# design.net
KiCad netlist of a schematic drawn in Altium Designer
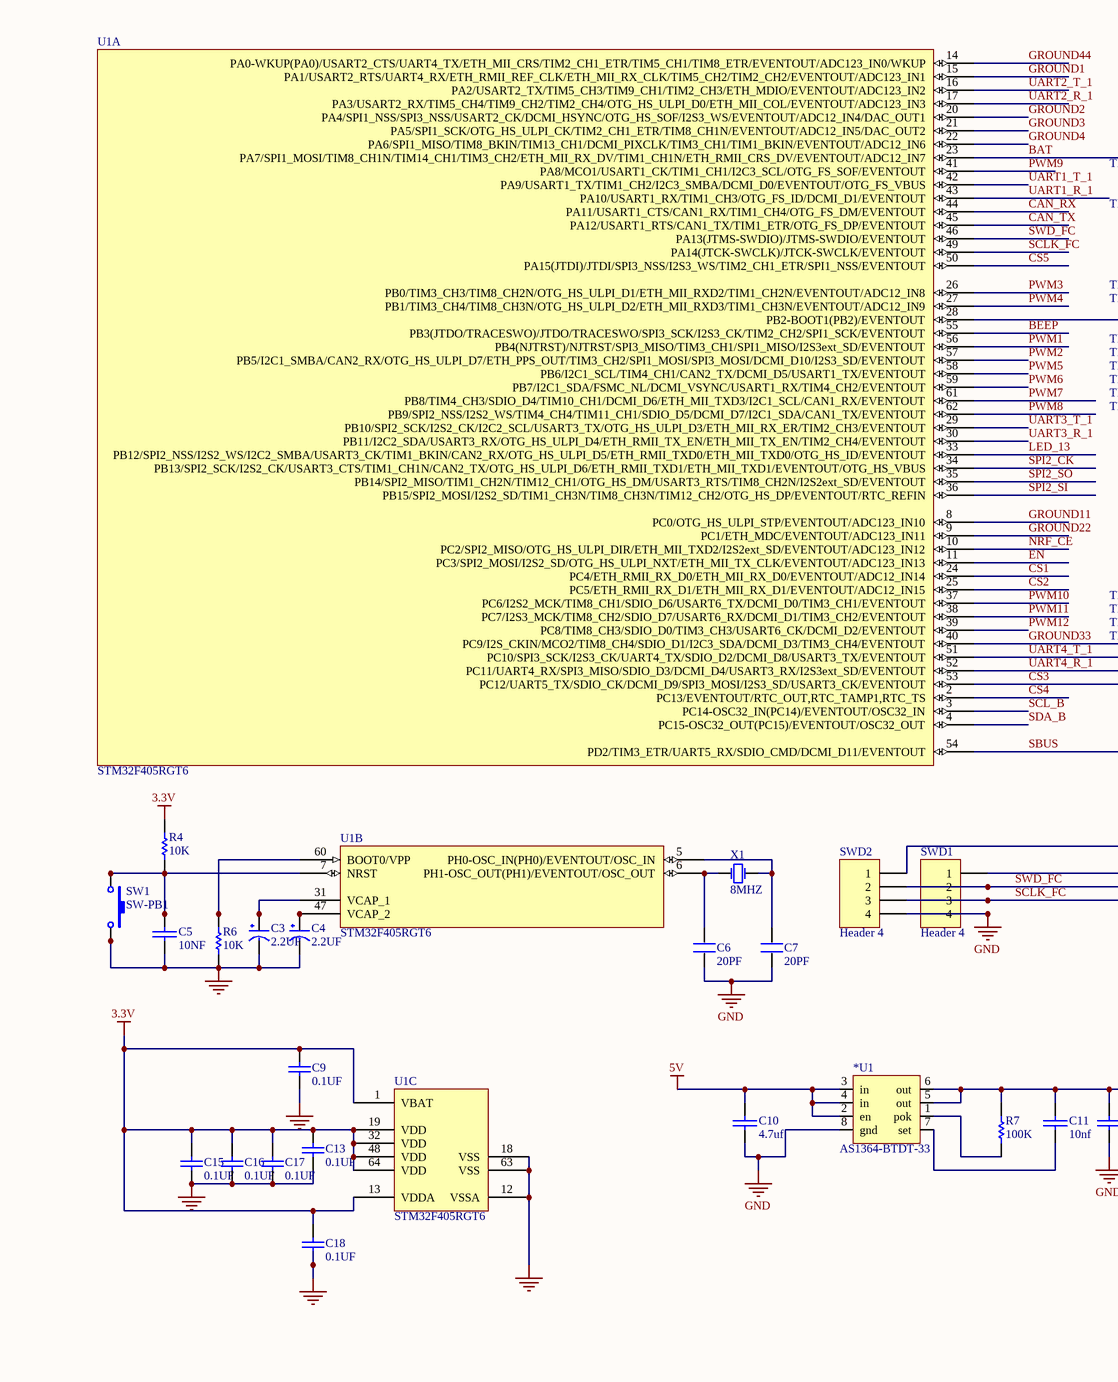
[diagram p0: 主控制器.SchDoc, top left]
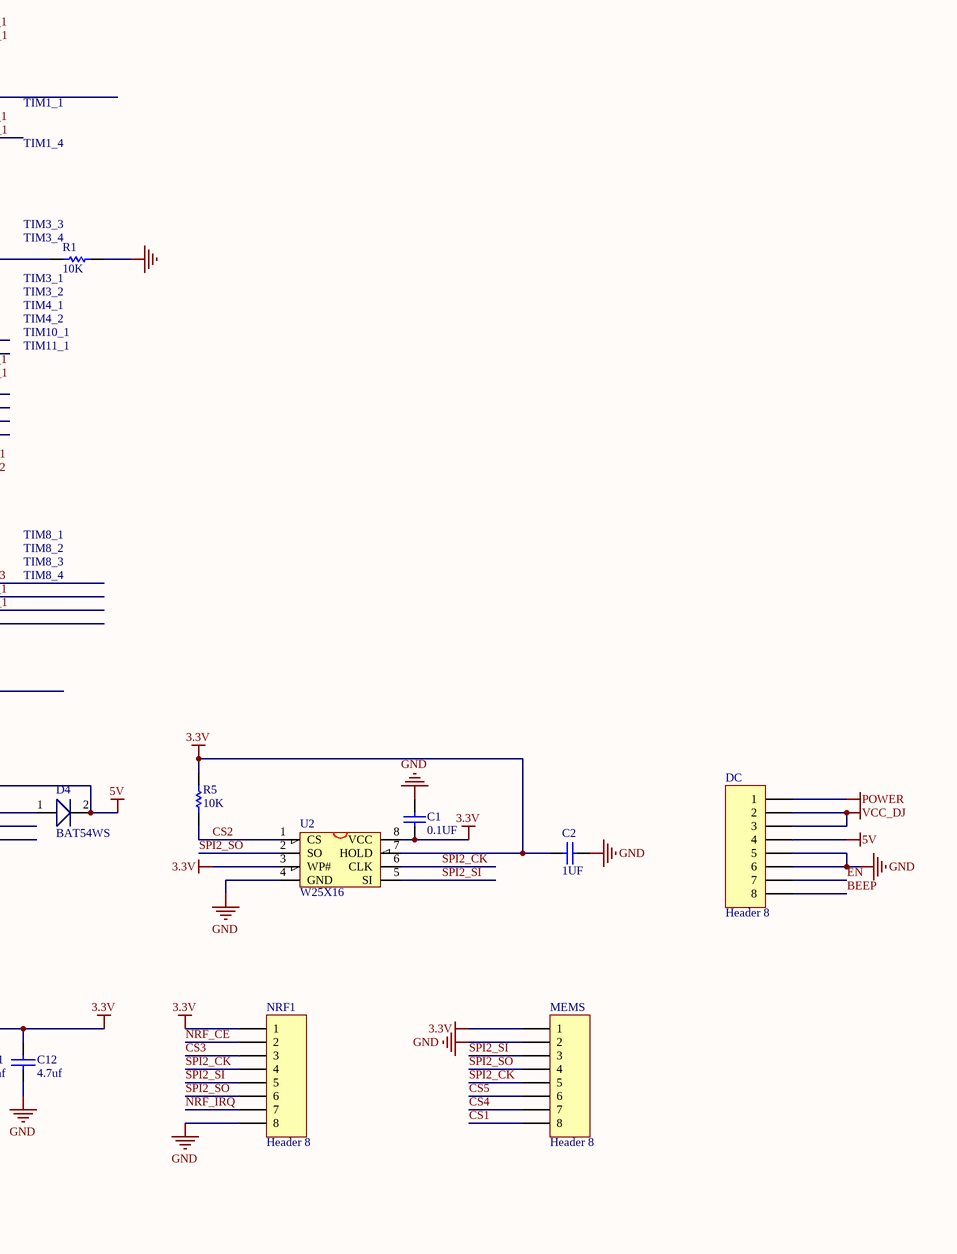
[diagram p1: 主控制器.SchDoc, top right]
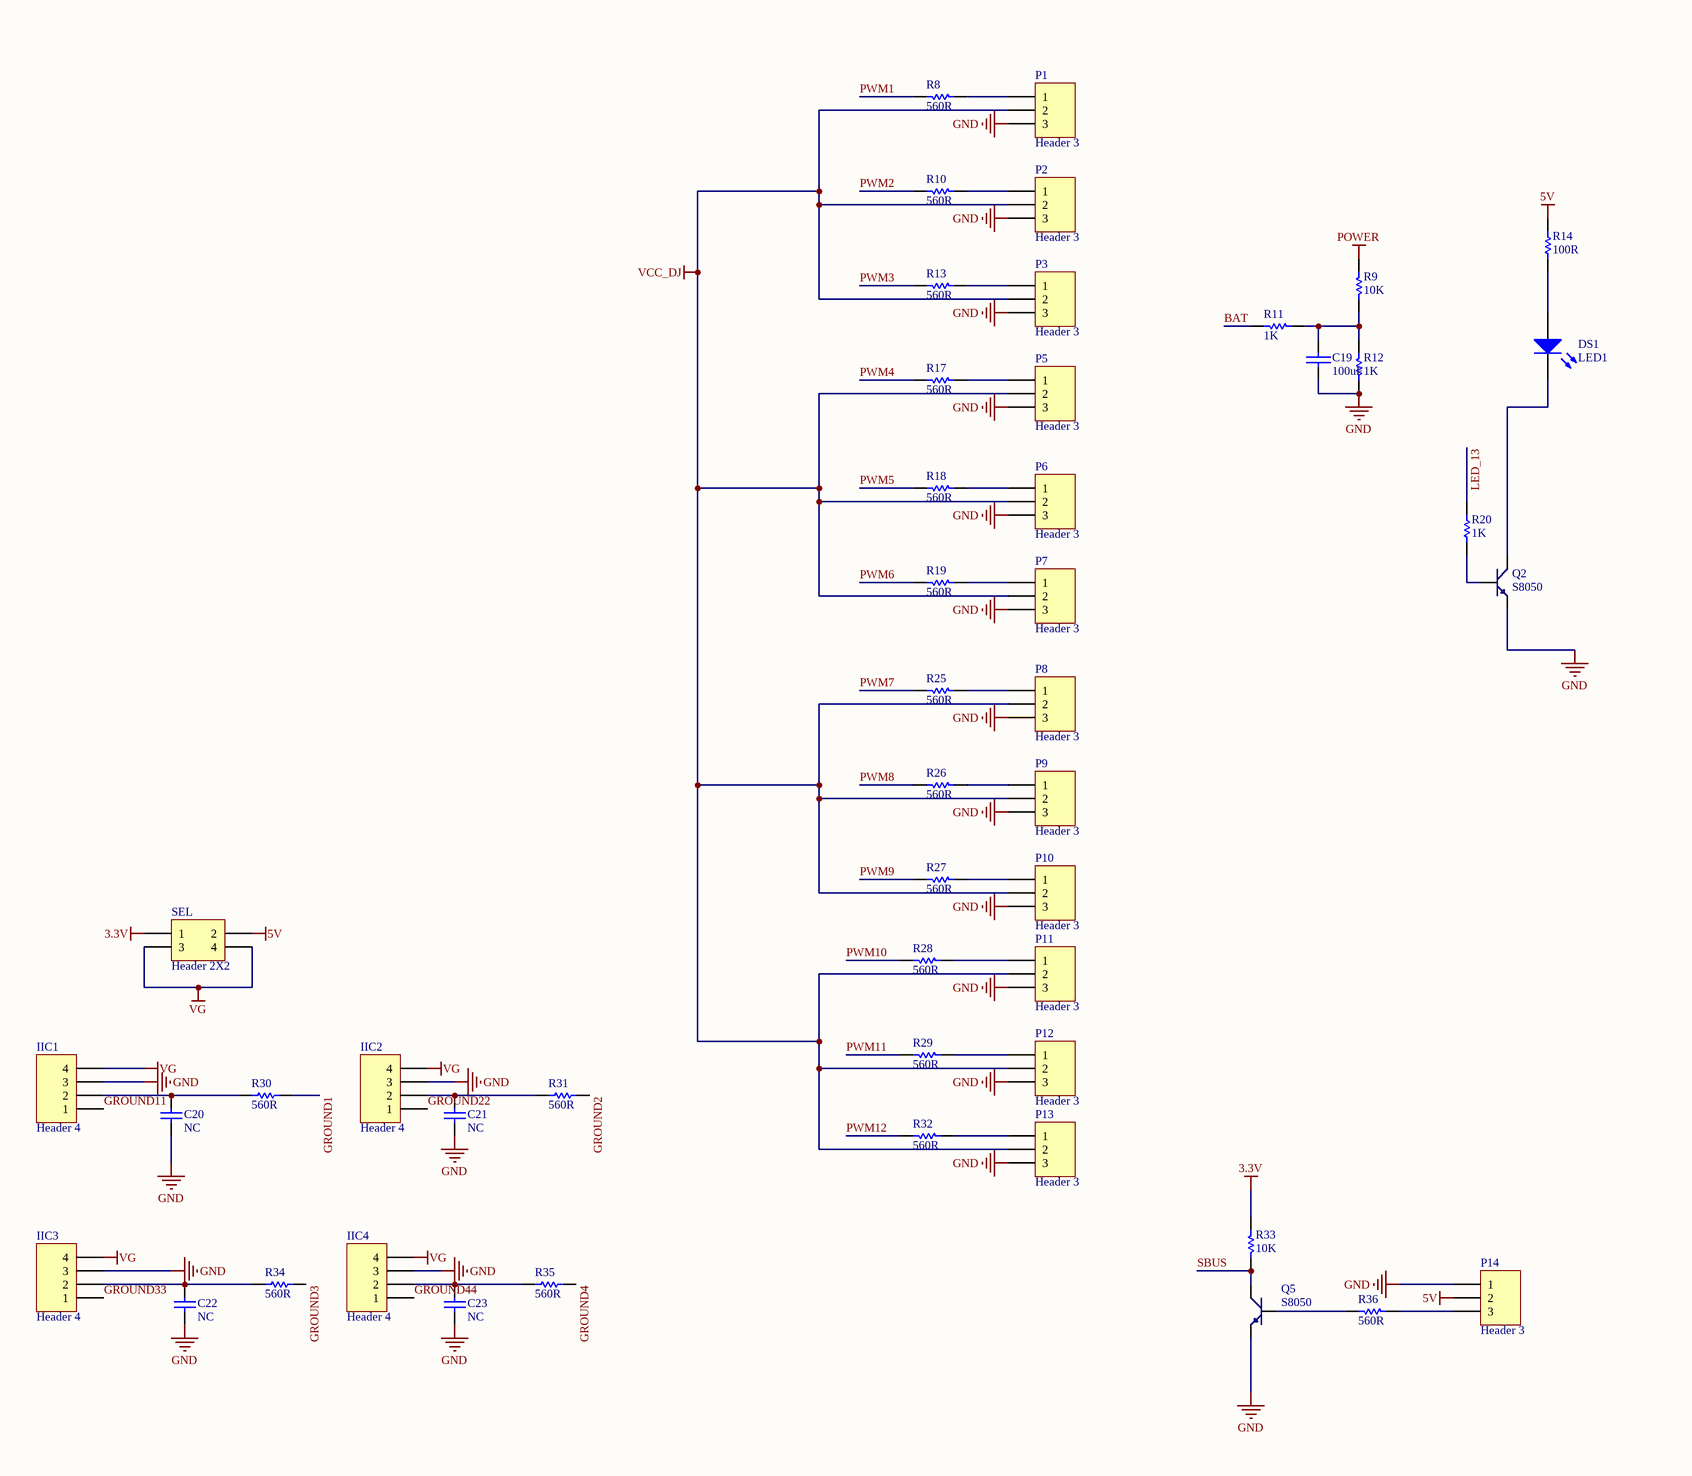
[diagram p2: 主控制器.SchDoc, bottom left]
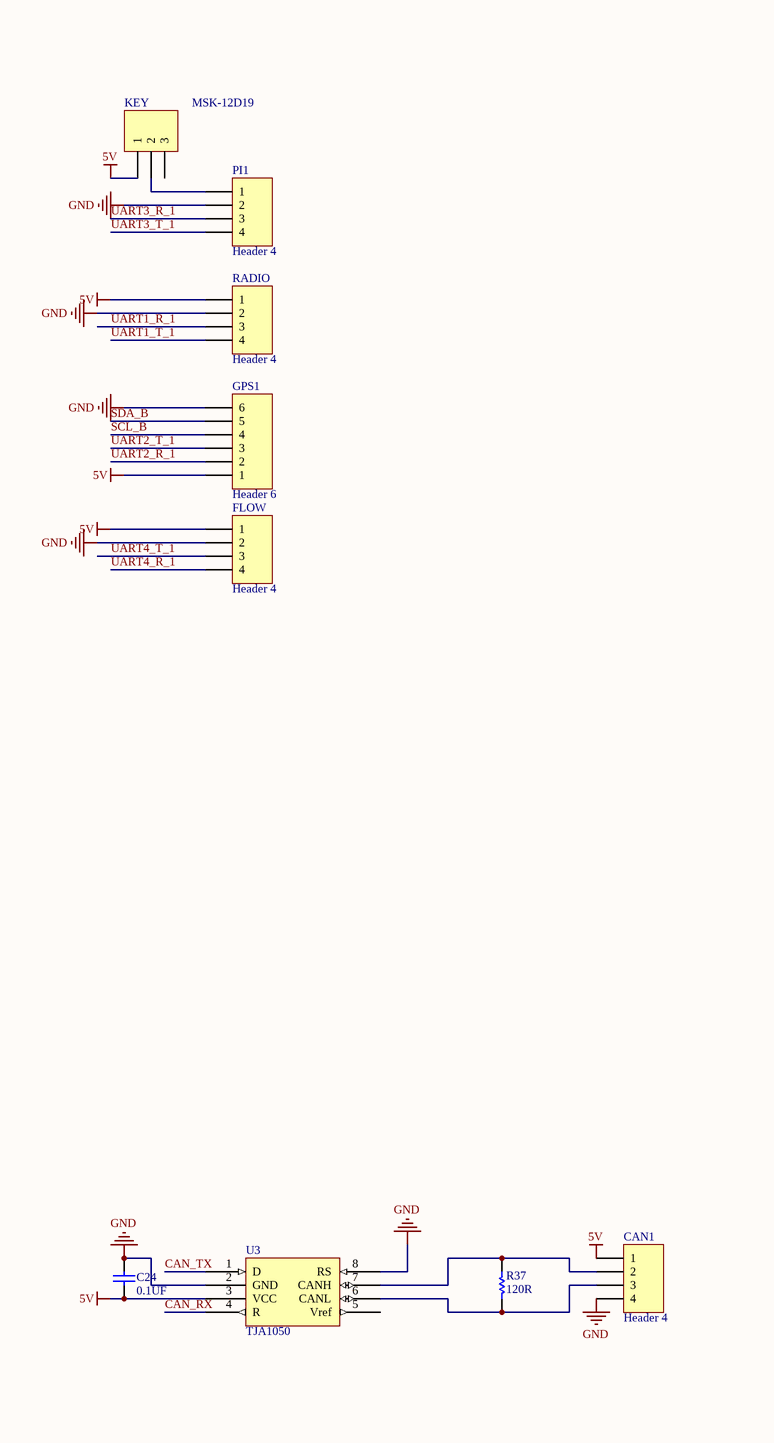
[diagram p3: 主控制器.SchDoc, bottom right]

(export (version "E")
  (design (tool "Eeschema 10.0.6"))
  (components
    (comp (ref "*U1")
      (value "AS1364-BTDT-33")
      (footprint "TDFN-8")
      (libsource (lib "Schlib1_hand") (part "AS1364-3.3V"))
    )
    (comp (ref "C1")
      (value "0.1UF")
      (footprint "C 0402")
      (description "Capacitor")
      (fields (field (name "PUBLISHER") "Altium Limited"))
      (libsource (lib "Miscellaneous Devices") (part "CAP"))
    )
    (comp (ref "C2")
      (value "1UF")
      (footprint "C 0402")
      (description "Capacitor")
      (fields (field (name "PUBLISHER") "Altium Limited"))
      (libsource (lib "Miscellaneous Devices") (part "CAP"))
    )
    (comp (ref "C3")
      (value "2.2UF")
      (footprint "C0603")
      (description "胆电容")
      (libsource (lib "stm32f429i") (part "CAP1"))
    )
    (comp (ref "C4")
      (value "2.2UF")
      (footprint "C0603")
      (description "胆电容")
      (libsource (lib "stm32f429i") (part "CAP1"))
    )
    (comp (ref "C5")
      (value "10NF")
      (footprint "C 0402")
      (description "Capacitor")
      (libsource (lib "*") (part "CAP"))
    )
    (comp (ref "C6")
      (value "20PF")
      (footprint "C 0402")
      (description "0805")
      (libsource (lib "stm32f429i") (part "C2"))
    )
    (comp (ref "C7")
      (value "20PF")
      (footprint "C 0402")
      (description "0805")
      (libsource (lib "stm32f429i") (part "C2"))
    )
    (comp (ref "C9")
      (value "0.1UF")
      (footprint "C 0402")
      (description "Capacitor")
      (fields (field (name "PUBLISHER") "Altium Limited"))
      (libsource (lib "Miscellaneous Devices") (part "CAP"))
    )
    (comp (ref "C10")
      (value "4.7uf")
      (footprint "C0603")
      (description "Capacitor")
      (libsource (lib "*") (part "CAP"))
    )
    (comp (ref "C11")
      (value "10nf")
      (footprint "C0603")
      (description "Capacitor")
      (libsource (lib "*") (part "CAP"))
    )
    (comp (ref "C12")
      (value "4.7uf")
      (footprint "C0603")
      (description "Capacitor")
      (libsource (lib "*") (part "CAP"))
    )
    (comp (ref "C13")
      (value "0.1UF")
      (footprint "C 0402")
      (description "Capacitor")
      (fields (field (name "PUBLISHER") "Altium Limited"))
      (libsource (lib "Miscellaneous Devices") (part "CAP"))
    )
    (comp (ref "C15")
      (value "0.1UF")
      (footprint "C 0402")
      (description "Capacitor")
      (fields (field (name "PUBLISHER") "Altium Limited"))
      (libsource (lib "Miscellaneous Devices") (part "CAP"))
    )
    (comp (ref "C16")
      (value "0.1UF")
      (footprint "C 0402")
      (description "Capacitor")
      (fields (field (name "PUBLISHER") "Altium Limited"))
      (libsource (lib "Miscellaneous Devices") (part "CAP"))
    )
    (comp (ref "C17")
      (value "0.1UF")
      (footprint "C 0402")
      (description "Capacitor")
      (fields (field (name "PUBLISHER") "Altium Limited"))
      (libsource (lib "Miscellaneous Devices") (part "CAP"))
    )
    (comp (ref "C18")
      (value "0.1UF")
      (footprint "C 0402")
      (description "Capacitor")
      (fields (field (name "PUBLISHER") "Altium Limited"))
      (libsource (lib "Miscellaneous Devices") (part "CAP"))
    )
    (comp (ref "C19")
      (value "100uF")
      (footprint "C0603")
      (description "Capacitor")
      (libsource (lib "*") (part "CAP"))
    )
    (comp (ref "C20")
      (value "NC")
      (footprint "C0603")
      (description "Capacitor")
      (fields (field (name "PUBLISHER") "Altium Limited"))
      (libsource (lib "Miscellaneous Devices") (part "CAP"))
    )
    (comp (ref "C21")
      (value "NC")
      (footprint "C0603")
      (description "Capacitor")
      (fields (field (name "PUBLISHER") "Altium Limited"))
      (libsource (lib "Miscellaneous Devices") (part "CAP"))
    )
    (comp (ref "C22")
      (value "NC")
      (footprint "C0603")
      (description "Capacitor")
      (fields (field (name "PUBLISHER") "Altium Limited"))
      (libsource (lib "Miscellaneous Devices") (part "CAP"))
    )
    (comp (ref "C23")
      (value "NC")
      (footprint "C0603")
      (description "Capacitor")
      (fields (field (name "PUBLISHER") "Altium Limited"))
      (libsource (lib "Miscellaneous Devices") (part "CAP"))
    )
    (comp (ref "C24")
      (value "0.1UF")
      (footprint "C 0402")
      (description "Capacitor")
      (fields (field (name "PUBLISHER") "Altium Limited"))
      (libsource (lib "Miscellaneous Devices") (part "CAP"))
    )
    (comp (ref "CAN1")
      (value "Header 4")
      (footprint "PH2.0-4")
      (description "Header, 4-Pin")
      (fields (field (name "PUBLISHER") "Altium Limited"))
      (libsource (lib "") (part "Header 4_1"))
    )
    (comp (ref "D4")
      (value "BAT54WS")
      (footprint "SOD-323")
      (description "单肖特基二极管")
      (libsource (lib "MiniFly ") (part "BAT54"))
    )
    (comp (ref "DC")
      (value "Header 8")
      (footprint "HDR1X8")
      (description "Header, 8-Pin")
      (fields (field (name "PUBLISHER") "Altium Limited"))
      (libsource (lib "") (part "Header 8_1"))
    )
    (comp (ref "DS1")
      (value "LED1")
      (footprint "SMDLED")
      (description "Typical RED, GREEN, YELLOW, AMBER GaAs LED")
      (fields (field (name "PUBLISHER") "Altium Limited"))
      (libsource (lib "EXPLORER") (part "LED2"))
    )
    (comp (ref "FLOW")
      (value "Header 4")
      (footprint "JST_GH_V4")
      (description "Header, 4-Pin")
      (fields (field (name "PUBLISHER") "Altium Limited"))
      (libsource (lib "") (part "Header 4_2"))
    )
    (comp (ref "GPS1")
      (value "Header 6")
      (footprint "JST_GH_V6")
      (description "Header, 6-Pin")
      (fields (field (name "PUBLISHER") "Altium Limited"))
      (libsource (lib "Miscellaneous Connectors") (part "Header 6"))
    )
    (comp (ref "IIC1")
      (value "Header 4")
      (footprint "JST_GH_V4")
      (description "Header, 4-Pin")
      (fields (field (name "PUBLISHER") "Altium Limited"))
      (libsource (lib "") (part "Header 4_1"))
    )
    (comp (ref "IIC2")
      (value "Header 4")
      (footprint "JST_GH_V4")
      (description "Header, 4-Pin")
      (fields (field (name "PUBLISHER") "Altium Limited"))
      (libsource (lib "") (part "Header 4_1"))
    )
    (comp (ref "IIC3")
      (value "Header 4")
      (footprint "JST_GH_V4")
      (description "Header, 4-Pin")
      (fields (field (name "PUBLISHER") "Altium Limited"))
      (libsource (lib "") (part "Header 4_1"))
    )
    (comp (ref "IIC4")
      (value "Header 4")
      (footprint "JST_GH_V4")
      (description "Header, 4-Pin")
      (fields (field (name "PUBLISHER") "Altium Limited"))
      (libsource (lib "") (part "Header 4_1"))
    )
    (comp (ref "KEY")
      (value "MSK-12D19")
      (footprint "HDR1X3")
      (description "Header, 3-Pin")
      (fields (field (name "PUBLISHER") "Altium Limited"))
      (libsource (lib "") (part "Header 3_1"))
    )
    (comp (ref "MEMS")
      (value "Header 8")
      (footprint "FH12-8S-1.0SH")
      (description "Header, 8-Pin")
      (fields (field (name "PUBLISHER") "Altium Limited"))
      (libsource (lib "Miscellaneous Connectors") (part "Header 8"))
    )
    (comp (ref "NRF1")
      (value "Header 8")
      (footprint "NRF")
      (description "Header, 8-Pin")
      (fields (field (name "PUBLISHER") "Altium Limited"))
      (libsource (lib "Miscellaneous Connectors") (part "Header 8"))
    )
    (comp (ref "P1")
      (value "Header 3")
      (footprint "HDR1X3")
      (description "Header, 3-Pin")
      (fields (field (name "PUBLISHER") "Altium Limited"))
      (libsource (lib "Miscellaneous Connectors") (part "Header 3"))
    )
    (comp (ref "P2")
      (value "Header 3")
      (footprint "HDR1X3")
      (description "Header, 3-Pin")
      (fields (field (name "PUBLISHER") "Altium Limited"))
      (libsource (lib "Miscellaneous Connectors") (part "Header 3"))
    )
    (comp (ref "P3")
      (value "Header 3")
      (footprint "HDR1X3")
      (description "Header, 3-Pin")
      (fields (field (name "PUBLISHER") "Altium Limited"))
      (libsource (lib "Miscellaneous Connectors") (part "Header 3"))
    )
    (comp (ref "P5")
      (value "Header 3")
      (footprint "HDR1X3")
      (description "Header, 3-Pin")
      (fields (field (name "PUBLISHER") "Altium Limited"))
      (libsource (lib "Miscellaneous Connectors") (part "Header 3"))
    )
    (comp (ref "P6")
      (value "Header 3")
      (footprint "HDR1X3")
      (description "Header, 3-Pin")
      (fields (field (name "PUBLISHER") "Altium Limited"))
      (libsource (lib "Miscellaneous Connectors") (part "Header 3"))
    )
    (comp (ref "P7")
      (value "Header 3")
      (footprint "HDR1X3")
      (description "Header, 3-Pin")
      (fields (field (name "PUBLISHER") "Altium Limited"))
      (libsource (lib "Miscellaneous Connectors") (part "Header 3"))
    )
    (comp (ref "P8")
      (value "Header 3")
      (footprint "HDR1X3")
      (description "Header, 3-Pin")
      (fields (field (name "PUBLISHER") "Altium Limited"))
      (libsource (lib "Miscellaneous Connectors") (part "Header 3"))
    )
    (comp (ref "P9")
      (value "Header 3")
      (footprint "HDR1X3")
      (description "Header, 3-Pin")
      (fields (field (name "PUBLISHER") "Altium Limited"))
      (libsource (lib "Miscellaneous Connectors") (part "Header 3"))
    )
    (comp (ref "P10")
      (value "Header 3")
      (footprint "HDR1X3")
      (description "Header, 3-Pin")
      (fields (field (name "PUBLISHER") "Altium Limited"))
      (libsource (lib "Miscellaneous Connectors") (part "Header 3"))
    )
    (comp (ref "P11")
      (value "Header 3")
      (footprint "HDR1X3")
      (description "Header, 3-Pin")
      (fields (field (name "PUBLISHER") "Altium Limited"))
      (libsource (lib "Miscellaneous Connectors") (part "Header 3"))
    )
    (comp (ref "P12")
      (value "Header 3")
      (footprint "HDR1X3")
      (description "Header, 3-Pin")
      (fields (field (name "PUBLISHER") "Altium Limited"))
      (libsource (lib "Miscellaneous Connectors") (part "Header 3"))
    )
    (comp (ref "P13")
      (value "Header 3")
      (footprint "HDR1X3")
      (description "Header, 3-Pin")
      (fields (field (name "PUBLISHER") "Altium Limited"))
      (libsource (lib "Miscellaneous Connectors") (part "Header 3"))
    )
    (comp (ref "P14")
      (value "Header 3")
      (footprint "HDR1X3")
      (description "Header, 3-Pin")
      (fields (field (name "PUBLISHER") "Altium Limited"))
      (libsource (lib "Miscellaneous Connectors") (part "Header 3"))
    )
    (comp (ref "PI1")
      (value "Header 4")
      (footprint "HDR1X4")
      (description "Header, 4-Pin")
      (fields (field (name "PUBLISHER") "Altium Limited"))
      (libsource (lib "") (part "Header 4_1"))
    )
    (comp (ref "Q2")
      (value "S8050")
      (footprint "SOT-23R")
      (description "8050/BCW846/BCW847")
      (libsource (lib "EXPLORER") (part "NPN"))
    )
    (comp (ref "Q5")
      (value "S8050")
      (footprint "SOT-23R")
      (description "8050/BCW846/BCW847")
      (libsource (lib "EXPLORER") (part "NPN"))
    )
    (comp (ref "R1")
      (value "10K")
      (footprint "R 0402")
      (description "0603")
      (libsource (lib "stm32f429i") (part "Res2"))
    )
    (comp (ref "R4")
      (value "10K")
      (footprint "R 0402")
      (description "0603")
      (libsource (lib "stm32f429i") (part "Res2"))
    )
    (comp (ref "R5")
      (value "10K")
      (footprint "R 0402")
      (description "0603")
      (libsource (lib "stm32f429i") (part "Res2"))
    )
    (comp (ref "R6")
      (value "10K")
      (footprint "R 0402")
      (description "0603")
      (libsource (lib "stm32f429i") (part "Res2"))
    )
    (comp (ref "R7")
      (value "100K")
      (footprint "R0603")
      (description "Resistor")
      (fields (field (name "PUBLISHER") "Altium Limited"))
      (libsource (lib "Miscellaneous Devices") (part "Res1"))
    )
    (comp (ref "R8")
      (value "560R")
      (footprint "R 0402")
      (description "0603")
      (libsource (lib "stm32f429i") (part "Res2"))
    )
    (comp (ref "R9")
      (value "10K")
      (footprint "R0603")
      (description "0603")
      (libsource (lib "stm32f429i") (part "Res2"))
    )
    (comp (ref "R10")
      (value "560R")
      (footprint "R 0402")
      (description "0603")
      (libsource (lib "stm32f429i") (part "Res2"))
    )
    (comp (ref "R11")
      (value "1K")
      (footprint "R0603")
      (description "0603")
      (libsource (lib "stm32f429i") (part "Res2"))
    )
    (comp (ref "R12")
      (value "1K")
      (footprint "R0603")
      (description "0603")
      (libsource (lib "stm32f429i") (part "Res2"))
    )
    (comp (ref "R13")
      (value "560R")
      (footprint "R 0402")
      (description "0603")
      (libsource (lib "stm32f429i") (part "Res2"))
    )
    (comp (ref "R14")
      (value "100R")
      (footprint "R 0402")
      (description "0603")
      (libsource (lib "stm32f429i") (part "Res2"))
    )
    (comp (ref "R17")
      (value "560R")
      (footprint "R 0402")
      (description "0603")
      (libsource (lib "stm32f429i") (part "Res2"))
    )
    (comp (ref "R18")
      (value "560R")
      (footprint "R 0402")
      (description "0603")
      (libsource (lib "stm32f429i") (part "Res2"))
    )
    (comp (ref "R19")
      (value "560R")
      (footprint "R 0402")
      (description "0603")
      (libsource (lib "stm32f429i") (part "Res2"))
    )
    (comp (ref "R20")
      (value "1K")
      (footprint "R 0402")
      (description "0603")
      (libsource (lib "stm32f429i") (part "Res2"))
    )
    (comp (ref "R25")
      (value "560R")
      (footprint "R 0402")
      (description "0603")
      (libsource (lib "stm32f429i") (part "Res2"))
    )
    (comp (ref "R26")
      (value "560R")
      (footprint "R 0402")
      (description "0603")
      (libsource (lib "stm32f429i") (part "Res2"))
    )
    (comp (ref "R27")
      (value "560R")
      (footprint "R 0402")
      (description "0603")
      (libsource (lib "stm32f429i") (part "Res2"))
    )
    (comp (ref "R28")
      (value "560R")
      (footprint "R 0402")
      (description "0603")
      (libsource (lib "stm32f429i") (part "Res2"))
    )
    (comp (ref "R29")
      (value "560R")
      (footprint "R 0402")
      (description "0603")
      (libsource (lib "stm32f429i") (part "Res2"))
    )
    (comp (ref "R30")
      (value "560R")
      (footprint "R0603")
      (description "Resistor")
      (fields (field (name "Comment") "1K") (field (name "PUBLISHER") "Altium Limited"))
      (libsource (lib "Miscellaneous Devices") (part "Res1"))
    )
    (comp (ref "R31")
      (value "560R")
      (footprint "R0603")
      (description "Resistor")
      (fields (field (name "Comment") "1K") (field (name "PUBLISHER") "Altium Limited"))
      (libsource (lib "Miscellaneous Devices") (part "Res1"))
    )
    (comp (ref "R32")
      (value "560R")
      (footprint "R 0402")
      (description "0603")
      (libsource (lib "stm32f429i") (part "Res2"))
    )
    (comp (ref "R33")
      (value "10K")
      (footprint "R 0402")
      (description "0603")
      (libsource (lib "stm32f429i") (part "Res2"))
    )
    (comp (ref "R34")
      (value "560R")
      (footprint "R0603")
      (description "Resistor")
      (fields (field (name "Comment") "1K") (field (name "PUBLISHER") "Altium Limited"))
      (libsource (lib "Miscellaneous Devices") (part "Res1"))
    )
    (comp (ref "R35")
      (value "560R")
      (footprint "R0603")
      (description "Resistor")
      (fields (field (name "Comment") "1K") (field (name "PUBLISHER") "Altium Limited"))
      (libsource (lib "Miscellaneous Devices") (part "Res1"))
    )
    (comp (ref "R36")
      (value "560R")
      (footprint "R 0402")
      (description "0603")
      (libsource (lib "stm32f429i") (part "Res2"))
    )
    (comp (ref "R37")
      (value "120R")
      (footprint "R0603")
      (description "0603")
      (libsource (lib "") (part "Res2_1"))
    )
    (comp (ref "RADIO")
      (value "Header 4")
      (footprint "JST_GH_V4")
      (description "Header, 4-Pin")
      (fields (field (name "PUBLISHER") "Altium Limited"))
      (libsource (lib "") (part "Header 4_2"))
    )
    (comp (ref "SEL")
      (value "Header 2X2")
      (footprint "HDR2X2")
      (description "Header, 2-Pin, Dual row")
      (fields (field (name "PUBLISHER") "Altium Limited"))
      (libsource (lib "Miscellaneous Connectors") (part "Header 2X2"))
    )
    (comp (ref "SW1")
      (value "SW-PB1")
      (footprint "KEY_SAD")
      (description "按键")
      (libsource (lib "stm32f429i") (part "SW-PB"))
    )
    (comp (ref "SWD1")
      (value "Header 4")
      (footprint "JST_GH_V4")
      (description "Header, 4-Pin")
      (fields (field (name "PUBLISHER") "Altium Limited"))
      (libsource (lib "Explorer STM32F407封装库") (part "Header 4"))
    )
    (comp (ref "SWD2")
      (value "Header 4")
      (footprint "HDR1X4")
      (description "Header, 4-Pin")
      (fields (field (name "PUBLISHER") "Altium Limited"))
      (libsource (lib "Miscellaneous Connectors") (part "Header 4"))
    )
    (comp (ref "U1")
      (value "STM32F405RGT6")
      (footprint "LQFP64_M")
      (libsource (lib "s_mcu") (part "STM32F405RGT6"))
    )
    (comp (ref "U2")
      (value "W25X16")
      (footprint "W25Q32FVZPIG")
      (description "W25X16;SST25VF016;MX25L1605")
      (libsource (lib "stm32f429i") (part "W25X16"))
    )
    (comp (ref "U3") (value "TJA1050") (footprint "SOP-8") (libsource (lib "EXPLORER") (part "SN65HVD230D")))
    (comp (ref "X1")
      (value "8MHZ")
      (footprint "PXCL")
      (description "Crystal Oscillator")
      (fields (field (name "PUBLISHER") "Altium Limited"))
      (libsource (lib "stm32f429i") (part "XTAL"))
    )
  )
  (nets
    (net (code "1") (name "/BAT") (class "Default")
      (node (ref "R11") (pin "1") (pinfunction "1_1") (pintype "passive"))
      (node (ref "U1") (pin "23") (pinfunction "PA7/SPI1_MOSI/TIM8_CH1N/TIM14_CH1/TIM3_CH2/ETH_MII_RX_DV/TIM1_CH1N/ETH_RMII_CRS_DV/EVENTOUT/ADC12_IN7_23") (pintype "bidirectional"))
    )
    (net (code "2") (name "/BEEP") (class "Default")
      (node (ref "DC") (pin "8") (pinfunction "8_8") (pintype "passive"))
      (node (ref "U1") (pin "55") (pinfunction "PB3(JTDO/TRACESWO)/JTDO/TRACESWO/SPI3_SCK/I2S3_CK/TIM2_CH2/SPI1_SCK/EVENTOUT_55") (pintype "bidirectional"))
    )
    (net (code "3") (name "/CAN_RX") (class "Default")
      (node (ref "U1") (pin "44") (pinfunction "PA11/USART1_CTS/CAN1_RX/TIM1_CH4/OTG_FS_DM/EVENTOUT_44") (pintype "bidirectional"))
      (node (ref "U3") (pin "4") (pinfunction "R_4") (pintype "output"))
    )
    (net (code "4") (name "/CAN_TX") (class "Default")
      (node (ref "U1") (pin "45") (pinfunction "PA12/USART1_RTS/CAN1_TX/TIM1_ETR/OTG_FS_DP/EVENTOUT_45") (pintype "bidirectional"))
      (node (ref "U3") (pin "1") (pinfunction "D_1") (pintype "input"))
    )
    (net (code "5") (name "/CS1") (class "Default")
      (node (ref "MEMS") (pin "8") (pinfunction "8_8") (pintype "passive"))
      (node (ref "U1") (pin "24") (pinfunction "PC4/ETH_RMII_RX_D0/ETH_MII_RX_D0/EVENTOUT/ADC12_IN14_24") (pintype "bidirectional"))
    )
    (net (code "6") (name "/CS2") (class "Default")
      (node (ref "R5") (pin "2") (pinfunction "2_2") (pintype "passive"))
      (node (ref "U1") (pin "25") (pinfunction "PC5/ETH_RMII_RX_D1/ETH_MII_RX_D1/EVENTOUT/ADC12_IN15_25") (pintype "bidirectional"))
      (node (ref "U2") (pin "1") (pinfunction "CS_1") (pintype "passive"))
    )
    (net (code "7") (name "/CS3") (class "Default")
      (node (ref "NRF1") (pin "3") (pinfunction "3_3") (pintype "passive"))
      (node (ref "U1") (pin "53") (pinfunction "PC12/UART5_TX/SDIO_CK/DCMI_D9/SPI3_MOSI/I2S3_SD/USART3_CK/EVENTOUT_53") (pintype "bidirectional"))
    )
    (net (code "8") (name "/CS4") (class "Default")
      (node (ref "MEMS") (pin "7") (pinfunction "7_7") (pintype "passive"))
      (node (ref "U1") (pin "2") (pinfunction "PC13/EVENTOUT/RTC_OUT,RTC_TAMP1,RTC_TS_2") (pintype "bidirectional"))
    )
    (net (code "9") (name "/CS5") (class "Default")
      (node (ref "MEMS") (pin "6") (pinfunction "6_6") (pintype "passive"))
      (node (ref "U1") (pin "50") (pinfunction "PA15(JTDI)/JTDI/SPI3_NSS/I2S3_WS/TIM2_CH1_ETR/SPI1_NSS/EVENTOUT_50") (pintype "bidirectional"))
    )
    (net (code "10") (name "/EN") (class "Default")
      (node (ref "DC") (pin "7") (pinfunction "7_7") (pintype "passive"))
      (node (ref "U1") (pin "11") (pinfunction "PC3/SPI2_MOSI/I2S2_SD/OTG_HS_ULPI_NXT/ETH_MII_TX_CLK/EVENTOUT/ADC123_IN13_11") (pintype "bidirectional"))
    )
    (net (code "11") (name "/GROUND1") (class "Default")
      (node (ref "R30") (pin "2") (pinfunction "2_2") (pintype "passive"))
      (node (ref "U1") (pin "15") (pinfunction "PA1/USART2_RTS/UART4_RX/ETH_RMII_REF_CLK/ETH_MII_RX_CLK/TIM5_CH2/TIM2_CH2/EVENTOUT/ADC123_IN1_15") (pintype "bidirectional"))
    )
    (net (code "12") (name "/GROUND2") (class "Default")
      (node (ref "R31") (pin "2") (pinfunction "2_2") (pintype "passive"))
      (node (ref "U1") (pin "20") (pinfunction "PA4/SPI1_NSS/SPI3_NSS/USART2_CK/DCMI_HSYNC/OTG_HS_SOF/I2S3_WS/EVENTOUT/ADC12_IN4/DAC_OUT1_20") (pintype "bidirectional"))
    )
    (net (code "13") (name "/GROUND3") (class "Default")
      (node (ref "R34") (pin "2") (pinfunction "2_2") (pintype "passive"))
      (node (ref "U1") (pin "21") (pinfunction "PA5/SPI1_SCK/OTG_HS_ULPI_CK/TIM2_CH1_ETR/TIM8_CH1N/EVENTOUT/ADC12_IN5/DAC_OUT2_21") (pintype "bidirectional"))
    )
    (net (code "14") (name "/GROUND4") (class "Default")
      (node (ref "R35") (pin "2") (pinfunction "2_2") (pintype "passive"))
      (node (ref "U1") (pin "22") (pinfunction "PA6/SPI1_MISO/TIM8_BKIN/TIM13_CH1/DCMI_PIXCLK/TIM3_CH1/TIM1_BKIN/EVENTOUT/ADC12_IN6_22") (pintype "bidirectional"))
    )
    (net (code "15") (name "/GROUND11") (class "Default")
      (node (ref "IIC1") (pin "1") (pinfunction "1_1") (pintype "passive"))
      (node (ref "U1") (pin "8") (pinfunction "PC0/OTG_HS_ULPI_STP/EVENTOUT/ADC123_IN10_8") (pintype "bidirectional"))
    )
    (net (code "16") (name "/GROUND22") (class "Default")
      (node (ref "IIC2") (pin "1") (pinfunction "1_1") (pintype "passive"))
      (node (ref "U1") (pin "9") (pinfunction "PC1/ETH_MDC/EVENTOUT/ADC123_IN11_9") (pintype "bidirectional"))
    )
    (net (code "17") (name "/GROUND33") (class "Default")
      (node (ref "IIC3") (pin "1") (pinfunction "1_1") (pintype "passive"))
      (node (ref "U1") (pin "40") (pinfunction "PC9/I2S_CKIN/MCO2/TIM8_CH4/SDIO_D1/I2C3_SDA/DCMI_D3/TIM3_CH4/EVENTOUT_40") (pintype "bidirectional"))
    )
    (net (code "18") (name "/GROUND44") (class "Default")
      (node (ref "IIC4") (pin "1") (pinfunction "1_1") (pintype "passive"))
      (node (ref "U1") (pin "14") (pinfunction "PA0-WKUP(PA0)/USART2_CTS/UART4_TX/ETH_MII_CRS/TIM2_CH1_ETR/TIM5_CH1/TIM8_ETR/EVENTOUT/ADC123_IN0/WKUP_14") (pintype "bidirectional"))
    )
    (net (code "19") (name "/LED_13") (class "Default")
      (node (ref "R20") (pin "1") (pinfunction "1_1") (pintype "passive"))
      (node (ref "U1") (pin "33") (pinfunction "PB12/SPI2_NSS/I2S2_WS/I2C2_SMBA/USART3_CK/TIM1_BKIN/CAN2_RX/OTG_HS_ULPI_D5/ETH_RMII_TXD0/ETH_MII_TXD0/OTG_HS_ID/EVENTOUT_33") (pintype "bidirectional"))
    )
    (net (code "20") (name "/NRF_CE") (class "Default")
      (node (ref "NRF1") (pin "2") (pinfunction "2_2") (pintype "passive"))
      (node (ref "U1") (pin "10") (pinfunction "PC2/SPI2_MISO/OTG_HS_ULPI_DIR/ETH_MII_TXD2/I2S2ext_SD/EVENTOUT/ADC123_IN12_10") (pintype "bidirectional"))
    )
    (net (code "21") (name "/NRF_IRQ") (class "Default")
      (node (ref "NRF1") (pin "7") (pinfunction "7_7") (pintype "passive"))
    )
    (net (code "22") (name "/PWM1") (class "Default")
      (node (ref "R8") (pin "1") (pinfunction "1_1") (pintype "passive"))
      (node (ref "U1") (pin "56") (pinfunction "PB4(NJTRST)/NJTRST/SPI3_MISO/TIM3_CH1/SPI1_MISO/I2S3ext_SD/EVENTOUT_56") (pintype "bidirectional"))
    )
    (net (code "23") (name "/PWM2") (class "Default")
      (node (ref "R10") (pin "1") (pinfunction "1_1") (pintype "passive"))
      (node (ref "U1") (pin "57") (pinfunction "PB5/I2C1_SMBA/CAN2_RX/OTG_HS_ULPI_D7/ETH_PPS_OUT/TIM3_CH2/SPI1_MOSI/SPI3_MOSI/DCMI_D10/I2S3_SD/EVENTOUT_57") (pintype "bidirectional"))
    )
    (net (code "24") (name "/PWM3") (class "Default")
      (node (ref "R13") (pin "1") (pinfunction "1_1") (pintype "passive"))
      (node (ref "U1") (pin "26") (pinfunction "PB0/TIM3_CH3/TIM8_CH2N/OTG_HS_ULPI_D1/ETH_MII_RXD2/TIM1_CH2N/EVENTOUT/ADC12_IN8_26") (pintype "bidirectional"))
    )
    (net (code "25") (name "/PWM4") (class "Default")
      (node (ref "R17") (pin "1") (pinfunction "1_1") (pintype "passive"))
      (node (ref "U1") (pin "27") (pinfunction "PB1/TIM3_CH4/TIM8_CH3N/OTG_HS_ULPI_D2/ETH_MII_RXD3/TIM1_CH3N/EVENTOUT/ADC12_IN9_27") (pintype "bidirectional"))
    )
    (net (code "26") (name "/PWM5") (class "Default")
      (node (ref "R18") (pin "1") (pinfunction "1_1") (pintype "passive"))
      (node (ref "U1") (pin "58") (pinfunction "PB6/I2C1_SCL/TIM4_CH1/CAN2_TX/DCMI_D5/USART1_TX/EVENTOUT_58") (pintype "bidirectional"))
    )
    (net (code "27") (name "/PWM6") (class "Default")
      (node (ref "R19") (pin "1") (pinfunction "1_1") (pintype "passive"))
      (node (ref "U1") (pin "59") (pinfunction "PB7/I2C1_SDA/FSMC_NL/DCMI_VSYNC/USART1_RX/TIM4_CH2/EVENTOUT_59") (pintype "bidirectional"))
    )
    (net (code "28") (name "/PWM7") (class "Default")
      (node (ref "R25") (pin "1") (pinfunction "1_1") (pintype "passive"))
      (node (ref "U1") (pin "61") (pinfunction "PB8/TIM4_CH3/SDIO_D4/TIM10_CH1/DCMI_D6/ETH_MII_TXD3/I2C1_SCL/CAN1_RX/EVENTOUT_61") (pintype "bidirectional"))
    )
    (net (code "29") (name "/PWM8") (class "Default")
      (node (ref "R26") (pin "1") (pinfunction "1_1") (pintype "passive"))
      (node (ref "U1") (pin "62") (pinfunction "PB9/SPI2_NSS/I2S2_WS/TIM4_CH4/TIM11_CH1/SDIO_D5/DCMI_D7/I2C1_SDA/CAN1_TX/EVENTOUT_62") (pintype "bidirectional"))
    )
    (net (code "30") (name "/PWM9") (class "Default")
      (node (ref "R27") (pin "1") (pinfunction "1_1") (pintype "passive"))
      (node (ref "U1") (pin "41") (pinfunction "PA8/MCO1/USART1_CK/TIM1_CH1/I2C3_SCL/OTG_FS_SOF/EVENTOUT_41") (pintype "bidirectional"))
    )
    (net (code "31") (name "/PWM10") (class "Default")
      (node (ref "R28") (pin "1") (pinfunction "1_1") (pintype "passive"))
      (node (ref "U1") (pin "37") (pinfunction "PC6/I2S2_MCK/TIM8_CH1/SDIO_D6/USART6_TX/DCMI_D0/TIM3_CH1/EVENTOUT_37") (pintype "bidirectional"))
    )
    (net (code "32") (name "/PWM11") (class "Default")
      (node (ref "R29") (pin "1") (pinfunction "1_1") (pintype "passive"))
      (node (ref "U1") (pin "38") (pinfunction "PC7/I2S3_MCK/TIM8_CH2/SDIO_D7/USART6_RX/DCMI_D1/TIM3_CH2/EVENTOUT_38") (pintype "bidirectional"))
    )
    (net (code "33") (name "/PWM12") (class "Default")
      (node (ref "R32") (pin "1") (pinfunction "1_1") (pintype "passive"))
      (node (ref "U1") (pin "39") (pinfunction "PC8/TIM8_CH3/SDIO_D0/TIM3_CH3/USART6_CK/DCMI_D2/EVENTOUT_39") (pintype "bidirectional"))
    )
    (net (code "34") (name "/SBUS") (class "Default")
      (node (ref "Q5") (pin "3") (pinfunction "C_3") (pintype "passive"))
      (node (ref "R33") (pin "1") (pinfunction "1_1") (pintype "passive"))
      (node (ref "U1") (pin "54") (pinfunction "PD2/TIM3_ETR/UART5_RX/SDIO_CMD/DCMI_D11/EVENTOUT_54") (pintype "bidirectional"))
    )
    (net (code "35") (name "/SCLK_FC") (class "Default")
      (node (ref "SWD1") (pin "3") (pinfunction "3_3") (pintype "passive"))
      (node (ref "SWD2") (pin "3") (pinfunction "3_3") (pintype "passive"))
      (node (ref "U1") (pin "49") (pinfunction "PA14(JTCK-SWCLK)/JTCK-SWCLK/EVENTOUT_49") (pintype "bidirectional"))
    )
    (net (code "36") (name "/SCL_B") (class "Default")
      (node (ref "GPS1") (pin "4") (pinfunction "4_4") (pintype "passive"))
      (node (ref "U1") (pin "3") (pinfunction "PC14-OSC32_IN(PC14)/EVENTOUT/OSC32_IN_3") (pintype "bidirectional"))
    )
    (net (code "37") (name "/SDA_B") (class "Default")
      (node (ref "GPS1") (pin "5") (pinfunction "5_5") (pintype "passive"))
      (node (ref "U1") (pin "4") (pinfunction "PC15-OSC32_OUT(PC15)/EVENTOUT/OSC32_OUT_4") (pintype "bidirectional"))
    )
    (net (code "38") (name "/SPI2_CK") (class "Default")
      (node (ref "MEMS") (pin "5") (pinfunction "5_5") (pintype "passive"))
      (node (ref "NRF1") (pin "4") (pinfunction "4_4") (pintype "passive"))
      (node (ref "U1") (pin "34") (pinfunction "PB13/SPI2_SCK/I2S2_CK/USART3_CTS/TIM1_CH1N/CAN2_TX/OTG_HS_ULPI_D6/ETH_RMII_TXD1/ETH_MII_TXD1/EVENTOUT/OTG_HS_VBUS_34") (pintype "bidirectional"))
      (node (ref "U2") (pin "6") (pinfunction "CLK_6") (pintype "passive"))
    )
    (net (code "39") (name "/SPI2_SI") (class "Default")
      (node (ref "MEMS") (pin "3") (pinfunction "3_3") (pintype "passive"))
      (node (ref "NRF1") (pin "5") (pinfunction "5_5") (pintype "passive"))
      (node (ref "U1") (pin "36") (pinfunction "PB15/SPI2_MOSI/I2S2_SD/TIM1_CH3N/TIM8_CH3N/TIM12_CH2/OTG_HS_DP/EVENTOUT/RTC_REFIN_36") (pintype "bidirectional"))
      (node (ref "U2") (pin "5") (pinfunction "SI_5") (pintype "passive"))
    )
    (net (code "40") (name "/SPI2_SO") (class "Default")
      (node (ref "MEMS") (pin "4") (pinfunction "4_4") (pintype "passive"))
      (node (ref "NRF1") (pin "6") (pinfunction "6_6") (pintype "passive"))
      (node (ref "U1") (pin "35") (pinfunction "PB14/SPI2_MISO/TIM1_CH2N/TIM12_CH1/OTG_HS_DM/USART3_RTS/TIM8_CH2N/I2S2ext_SD/EVENTOUT_35") (pintype "bidirectional"))
      (node (ref "U2") (pin "2") (pinfunction "SO_2") (pintype "passive"))
    )
    (net (code "41") (name "/SWD_FC") (class "Default")
      (node (ref "SWD1") (pin "2") (pinfunction "2_2") (pintype "passive"))
      (node (ref "SWD2") (pin "2") (pinfunction "2_2") (pintype "passive"))
      (node (ref "U1") (pin "46") (pinfunction "PA13(JTMS-SWDIO)/JTMS-SWDIO/EVENTOUT_46") (pintype "bidirectional"))
    )
    (net (code "42") (name "/UART1_R_1") (class "Default")
      (node (ref "RADIO") (pin "3") (pinfunction "3_3") (pintype "passive"))
      (node (ref "U1") (pin "43") (pinfunction "PA10/USART1_RX/TIM1_CH3/OTG_FS_ID/DCMI_D1/EVENTOUT_43") (pintype "bidirectional"))
    )
    (net (code "43") (name "/UART1_T_1") (class "Default")
      (node (ref "RADIO") (pin "4") (pinfunction "4_4") (pintype "passive"))
      (node (ref "U1") (pin "42") (pinfunction "PA9/USART1_TX/TIM1_CH2/I2C3_SMBA/DCMI_D0/EVENTOUT/OTG_FS_VBUS_42") (pintype "bidirectional"))
    )
    (net (code "44") (name "/UART2_R_1") (class "Default")
      (node (ref "GPS1") (pin "2") (pinfunction "2_2") (pintype "passive"))
      (node (ref "U1") (pin "17") (pinfunction "PA3/USART2_RX/TIM5_CH4/TIM9_CH2/TIM2_CH4/OTG_HS_ULPI_D0/ETH_MII_COL/EVENTOUT/ADC123_IN3_17") (pintype "bidirectional"))
    )
    (net (code "45") (name "/UART2_T_1") (class "Default")
      (node (ref "GPS1") (pin "3") (pinfunction "3_3") (pintype "passive"))
      (node (ref "U1") (pin "16") (pinfunction "PA2/USART2_TX/TIM5_CH3/TIM9_CH1/TIM2_CH3/ETH_MDIO/EVENTOUT/ADC123_IN2_16") (pintype "bidirectional"))
    )
    (net (code "46") (name "/UART3_R_1") (class "Default")
      (node (ref "PI1") (pin "3") (pinfunction "3_3") (pintype "passive"))
      (node (ref "U1") (pin "30") (pinfunction "PB11/I2C2_SDA/USART3_RX/OTG_HS_ULPI_D4/ETH_RMII_TX_EN/ETH_MII_TX_EN/TIM2_CH4/EVENTOUT_30") (pintype "bidirectional"))
    )
    (net (code "47") (name "/UART3_T_1") (class "Default")
      (node (ref "PI1") (pin "4") (pinfunction "4_4") (pintype "passive"))
      (node (ref "U1") (pin "29") (pinfunction "PB10/SPI2_SCK/I2S2_CK/I2C2_SCL/USART3_TX/OTG_HS_ULPI_D3/ETH_MII_RX_ER/TIM2_CH3/EVENTOUT_29") (pintype "bidirectional"))
    )
    (net (code "48") (name "/UART4_R_1") (class "Default")
      (node (ref "FLOW") (pin "4") (pinfunction "4_4") (pintype "passive"))
      (node (ref "U1") (pin "52") (pinfunction "PC11/UART4_RX/SPI3_MISO/SDIO_D3/DCMI_D4/USART3_RX/I2S3ext_SD/EVENTOUT_52") (pintype "bidirectional"))
    )
    (net (code "49") (name "/UART4_T_1") (class "Default")
      (node (ref "FLOW") (pin "3") (pinfunction "3_3") (pintype "passive"))
      (node (ref "U1") (pin "51") (pinfunction "PC10/SPI3_SCK/I2S3_CK/UART4_TX/SDIO_D2/DCMI_D8/USART3_TX/EVENTOUT_51") (pintype "bidirectional"))
    )
    (net (code "50") (name "3.3V") (class "Default")
      (node (ref "*U1") (pin "5") (pinfunction "out_5") (pintype "passive"))
      (node (ref "*U1") (pin "6") (pinfunction "out_6") (pintype "passive"))
      (node (ref "C1") (pin "1") (pinfunction "1_1") (pintype "passive"))
      (node (ref "C11") (pin "1") (pinfunction "1_1") (pintype "passive"))
      (node (ref "C12") (pin "1") (pinfunction "1_1") (pintype "passive"))
      (node (ref "C13") (pin "1") (pinfunction "1_1") (pintype "passive"))
      (node (ref "C15") (pin "1") (pinfunction "1_1") (pintype "passive"))
      (node (ref "C16") (pin "1") (pinfunction "1_1") (pintype "passive"))
      (node (ref "C17") (pin "1") (pinfunction "1_1") (pintype "passive"))
      (node (ref "C18") (pin "1") (pinfunction "1_1") (pintype "passive"))
      (node (ref "C2") (pin "2") (pinfunction "2_2") (pintype "passive"))
      (node (ref "C9") (pin "1") (pinfunction "1_1") (pintype "passive"))
      (node (ref "MEMS") (pin "1") (pinfunction "1_1") (pintype "passive"))
      (node (ref "NRF1") (pin "1") (pinfunction "1_1") (pintype "passive"))
      (node (ref "R33") (pin "2") (pinfunction "2_2") (pintype "passive"))
      (node (ref "R4") (pin "2") (pinfunction "2_2") (pintype "passive"))
      (node (ref "R5") (pin "1") (pinfunction "1_1") (pintype "passive"))
      (node (ref "R7") (pin "1") (pinfunction "1_1") (pintype "passive"))
      (node (ref "SEL") (pin "1") (pinfunction "1_1") (pintype "passive"))
      (node (ref "U1") (pin "1") (pinfunction "VBAT_1") (pintype "power_in"))
      (node (ref "U1") (pin "13") (pinfunction "VDDA_13") (pintype "power_in"))
      (node (ref "U1") (pin "19") (pinfunction "VDD_19") (pintype "power_in"))
      (node (ref "U1") (pin "32") (pinfunction "VDD_32") (pintype "power_in"))
      (node (ref "U1") (pin "48") (pinfunction "VDD_48") (pintype "power_in"))
      (node (ref "U1") (pin "64") (pinfunction "VDD_64") (pintype "power_in"))
      (node (ref "U2") (pin "3") (pinfunction "WP#_3") (pintype "passive"))
      (node (ref "U2") (pin "7") (pinfunction "HOLD_7") (pintype "passive"))
      (node (ref "U2") (pin "8") (pinfunction "VCC_8") (pintype "passive"))
    )
    (net (code "51") (name "5V") (class "Default")
      (node (ref "*U1") (pin "2") (pinfunction "en_2") (pintype "passive"))
      (node (ref "*U1") (pin "3") (pinfunction "in_3") (pintype "passive"))
      (node (ref "*U1") (pin "4") (pinfunction "in_4") (pintype "passive"))
      (node (ref "C10") (pin "1") (pinfunction "1_1") (pintype "passive"))
      (node (ref "C24") (pin "2") (pinfunction "2_2") (pintype "passive"))
      (node (ref "CAN1") (pin "1") (pinfunction "1_1") (pintype "passive"))
      (node (ref "D4") (pin "2") (pinfunction "2_2") (pintype "passive"))
      (node (ref "DC") (pin "4") (pinfunction "4_4") (pintype "passive"))
      (node (ref "FLOW") (pin "1") (pinfunction "1_1") (pintype "passive"))
      (node (ref "GPS1") (pin "1") (pinfunction "1_1") (pintype "passive"))
      (node (ref "KEY") (pin "1") (pinfunction "1_1") (pintype "passive"))
      (node (ref "P14") (pin "2") (pinfunction "2_2") (pintype "passive"))
      (node (ref "R14") (pin "1") (pinfunction "1_1") (pintype "passive"))
      (node (ref "RADIO") (pin "1") (pinfunction "1_1") (pintype "passive"))
      (node (ref "SEL") (pin "2") (pinfunction "2_2") (pintype "passive"))
      (node (ref "SWD2") (pin "1") (pinfunction "1_1") (pintype "passive"))
      (node (ref "U3") (pin "3") (pinfunction "VCC_3") (pintype "power_in"))
    )
    (net (code "52") (name "GND") (class "Default")
      (node (ref "*U1") (pin "8") (pinfunction "gnd_8") (pintype "passive"))
      (node (ref "C1") (pin "2") (pinfunction "2_2") (pintype "passive"))
      (node (ref "C10") (pin "2") (pinfunction "2_2") (pintype "passive"))
      (node (ref "C12") (pin "2") (pinfunction "2_2") (pintype "passive"))
      (node (ref "C13") (pin "2") (pinfunction "2_2") (pintype "passive"))
      (node (ref "C15") (pin "2") (pinfunction "2_2") (pintype "passive"))
      (node (ref "C16") (pin "2") (pinfunction "2_2") (pintype "passive"))
      (node (ref "C17") (pin "2") (pinfunction "2_2") (pintype "passive"))
      (node (ref "C18") (pin "2") (pinfunction "2_2") (pintype "passive"))
      (node (ref "C19") (pin "2") (pinfunction "2_2") (pintype "passive"))
      (node (ref "C2") (pin "1") (pinfunction "1_1") (pintype "passive"))
      (node (ref "C20") (pin "2") (pinfunction "2_2") (pintype "passive"))
      (node (ref "C21") (pin "2") (pinfunction "2_2") (pintype "passive"))
      (node (ref "C22") (pin "2") (pinfunction "2_2") (pintype "passive"))
      (node (ref "C23") (pin "2") (pinfunction "2_2") (pintype "passive"))
      (node (ref "C24") (pin "1") (pinfunction "1_1") (pintype "passive"))
      (node (ref "C3") (pin "2") (pinfunction "GND_2") (pintype "passive"))
      (node (ref "C4") (pin "2") (pinfunction "GND_2") (pintype "passive"))
      (node (ref "C5") (pin "1") (pinfunction "1_1") (pintype "passive"))
      (node (ref "C6") (pin "1") (pintype "passive"))
      (node (ref "C7") (pin "1") (pintype "passive"))
      (node (ref "C9") (pin "2") (pinfunction "2_2") (pintype "passive"))
      (node (ref "CAN1") (pin "4") (pinfunction "4_4") (pintype "passive"))
      (node (ref "DC") (pin "5") (pinfunction "5_5") (pintype "passive"))
      (node (ref "DC") (pin "6") (pinfunction "6_6") (pintype "passive"))
      (node (ref "FLOW") (pin "2") (pinfunction "2_2") (pintype "passive"))
      (node (ref "GPS1") (pin "6") (pinfunction "6_6") (pintype "passive"))
      (node (ref "IIC1") (pin "3") (pinfunction "3_3") (pintype "passive"))
      (node (ref "IIC2") (pin "3") (pinfunction "3_3") (pintype "passive"))
      (node (ref "IIC3") (pin "3") (pinfunction "3_3") (pintype "passive"))
      (node (ref "IIC4") (pin "3") (pinfunction "3_3") (pintype "passive"))
      (node (ref "MEMS") (pin "2") (pinfunction "2_2") (pintype "passive"))
      (node (ref "NRF1") (pin "8") (pinfunction "8_8") (pintype "passive"))
      (node (ref "P1") (pin "3") (pinfunction "3_3") (pintype "passive"))
      (node (ref "P10") (pin "3") (pinfunction "3_3") (pintype "passive"))
      (node (ref "P11") (pin "3") (pinfunction "3_3") (pintype "passive"))
      (node (ref "P12") (pin "3") (pinfunction "3_3") (pintype "passive"))
      (node (ref "P13") (pin "3") (pinfunction "3_3") (pintype "passive"))
      (node (ref "P14") (pin "1") (pinfunction "1_1") (pintype "passive"))
      (node (ref "P2") (pin "3") (pinfunction "3_3") (pintype "passive"))
      (node (ref "P3") (pin "3") (pinfunction "3_3") (pintype "passive"))
      (node (ref "P5") (pin "3") (pinfunction "3_3") (pintype "passive"))
      (node (ref "P6") (pin "3") (pinfunction "3_3") (pintype "passive"))
      (node (ref "P7") (pin "3") (pinfunction "3_3") (pintype "passive"))
      (node (ref "P8") (pin "3") (pinfunction "3_3") (pintype "passive"))
      (node (ref "P9") (pin "3") (pinfunction "3_3") (pintype "passive"))
      (node (ref "PI1") (pin "2") (pinfunction "2_2") (pintype "passive"))
      (node (ref "Q2") (pin "1") (pinfunction "E_1") (pintype "passive"))
      (node (ref "Q5") (pin "1") (pinfunction "E_1") (pintype "passive"))
      (node (ref "R1") (pin "1") (pinfunction "1_1") (pintype "passive"))
      (node (ref "R12") (pin "1") (pinfunction "1_1") (pintype "passive"))
      (node (ref "R6") (pin "1") (pinfunction "1_1") (pintype "passive"))
      (node (ref "RADIO") (pin "2") (pinfunction "2_2") (pintype "passive"))
      (node (ref "SW1") (pin "1") (pinfunction "1_1") (pintype "passive"))
      (node (ref "SWD1") (pin "4") (pinfunction "4_4") (pintype "passive"))
      (node (ref "SWD2") (pin "4") (pinfunction "4_4") (pintype "passive"))
      (node (ref "U1") (pin "12") (pinfunction "VSSA_12") (pintype "power_in"))
      (node (ref "U1") (pin "18") (pinfunction "VSS_18") (pintype "power_in"))
      (node (ref "U1") (pin "63") (pinfunction "VSS_63") (pintype "power_in"))
      (node (ref "U2") (pin "4") (pinfunction "GND_4") (pintype "passive"))
      (node (ref "U3") (pin "2") (pinfunction "GND_2") (pintype "power_in"))
      (node (ref "U3") (pin "8") (pinfunction "RS_8") (pintype "input"))
    )
    (net (code "53") (name "Net-(*U1-pok)") (class "Default")
      (node (ref "*U1") (pin "1") (pinfunction "pok_1") (pintype "passive"))
      (node (ref "R7") (pin "2") (pinfunction "2_2") (pintype "passive"))
    )
    (net (code "54") (name "Net-(*U1-set)") (class "Default")
      (node (ref "*U1") (pin "7") (pinfunction "set_7") (pintype "passive"))
      (node (ref "C11") (pin "2") (pinfunction "2_2") (pintype "passive"))
    )
    (net (code "55") (name "Net-(C3-VCC)") (class "Default")
      (node (ref "C3") (pin "1") (pinfunction "VCC_1") (pintype "passive"))
      (node (ref "U1") (pin "31") (pinfunction "VCAP_1_31") (pintype "power_in"))
    )
    (net (code "56") (name "Net-(C4-VCC)") (class "Default")
      (node (ref "C4") (pin "1") (pinfunction "VCC_1") (pintype "passive"))
      (node (ref "U1") (pin "47") (pinfunction "VCAP_2_47") (pintype "power_in"))
    )
    (net (code "57") (name "Net-(C19-Pad1)") (class "Default")
      (node (ref "C19") (pin "1") (pinfunction "1_1") (pintype "passive"))
      (node (ref "R11") (pin "2") (pinfunction "2_2") (pintype "passive"))
      (node (ref "R12") (pin "2") (pinfunction "2_2") (pintype "passive"))
      (node (ref "R9") (pin "1") (pinfunction "1_1") (pintype "passive"))
    )
    (net (code "58") (name "Net-(C20-Pad1)") (class "Default")
      (node (ref "C20") (pin "1") (pinfunction "1_1") (pintype "passive"))
      (node (ref "IIC1") (pin "2") (pinfunction "2_2") (pintype "passive"))
      (node (ref "R30") (pin "1") (pinfunction "1_1") (pintype "passive"))
    )
    (net (code "59") (name "Net-(C21-Pad1)") (class "Default")
      (node (ref "C21") (pin "1") (pinfunction "1_1") (pintype "passive"))
      (node (ref "IIC2") (pin "2") (pinfunction "2_2") (pintype "passive"))
      (node (ref "R31") (pin "1") (pinfunction "1_1") (pintype "passive"))
    )
    (net (code "60") (name "Net-(C22-Pad1)") (class "Default")
      (node (ref "C22") (pin "1") (pinfunction "1_1") (pintype "passive"))
      (node (ref "IIC3") (pin "2") (pinfunction "2_2") (pintype "passive"))
      (node (ref "R34") (pin "1") (pinfunction "1_1") (pintype "passive"))
    )
    (net (code "61") (name "Net-(C23-Pad1)") (class "Default")
      (node (ref "C23") (pin "1") (pinfunction "1_1") (pintype "passive"))
      (node (ref "IIC4") (pin "2") (pinfunction "2_2") (pintype "passive"))
      (node (ref "R35") (pin "1") (pinfunction "1_1") (pintype "passive"))
    )
    (net (code "62") (name "Net-(D4-Pad1)") (class "Default")
      (node (ref "D4") (pin "1") (pinfunction "1_1") (pintype "passive"))
      (node (ref "SWD1") (pin "1") (pinfunction "1_1") (pintype "passive"))
    )
    (net (code "63") (name "Net-(DS1-A)") (class "Default")
      (node (ref "DS1") (pin "1") (pinfunction "A_1") (pintype "passive"))
      (node (ref "R14") (pin "2") (pinfunction "2_2") (pintype "passive"))
    )
    (net (code "64") (name "Net-(DS1-K)") (class "Default")
      (node (ref "DS1") (pin "2") (pinfunction "K_2") (pintype "passive"))
      (node (ref "Q2") (pin "3") (pinfunction "C_3") (pintype "passive"))
    )
    (net (code "65") (name "Net-(KEY-Pad2)") (class "Default")
      (node (ref "KEY") (pin "2") (pinfunction "2_2") (pintype "passive"))
      (node (ref "PI1") (pin "1") (pinfunction "1_1") (pintype "passive"))
    )
    (net (code "66") (name "Net-(P1-Pad1)") (class "Default")
      (node (ref "P1") (pin "1") (pinfunction "1_1") (pintype "passive"))
      (node (ref "R8") (pin "2") (pinfunction "2_2") (pintype "passive"))
    )
    (net (code "67") (name "Net-(P2-Pad1)") (class "Default")
      (node (ref "P2") (pin "1") (pinfunction "1_1") (pintype "passive"))
      (node (ref "R10") (pin "2") (pinfunction "2_2") (pintype "passive"))
    )
    (net (code "68") (name "Net-(P3-Pad1)") (class "Default")
      (node (ref "P3") (pin "1") (pinfunction "1_1") (pintype "passive"))
      (node (ref "R13") (pin "2") (pinfunction "2_2") (pintype "passive"))
    )
    (net (code "69") (name "Net-(P5-Pad1)") (class "Default")
      (node (ref "P5") (pin "1") (pinfunction "1_1") (pintype "passive"))
      (node (ref "R17") (pin "2") (pinfunction "2_2") (pintype "passive"))
    )
    (net (code "70") (name "Net-(P6-Pad1)") (class "Default")
      (node (ref "P6") (pin "1") (pinfunction "1_1") (pintype "passive"))
      (node (ref "R18") (pin "2") (pinfunction "2_2") (pintype "passive"))
    )
    (net (code "71") (name "Net-(P7-Pad1)") (class "Default")
      (node (ref "P7") (pin "1") (pinfunction "1_1") (pintype "passive"))
      (node (ref "R19") (pin "2") (pinfunction "2_2") (pintype "passive"))
    )
    (net (code "72") (name "Net-(P8-Pad1)") (class "Default")
      (node (ref "P8") (pin "1") (pinfunction "1_1") (pintype "passive"))
      (node (ref "R25") (pin "2") (pinfunction "2_2") (pintype "passive"))
    )
    (net (code "73") (name "Net-(P9-Pad1)") (class "Default")
      (node (ref "P9") (pin "1") (pinfunction "1_1") (pintype "passive"))
      (node (ref "R26") (pin "2") (pinfunction "2_2") (pintype "passive"))
    )
    (net (code "74") (name "Net-(P10-Pad1)") (class "Default")
      (node (ref "P10") (pin "1") (pinfunction "1_1") (pintype "passive"))
      (node (ref "R27") (pin "2") (pinfunction "2_2") (pintype "passive"))
    )
    (net (code "75") (name "Net-(P11-Pad1)") (class "Default")
      (node (ref "P11") (pin "1") (pinfunction "1_1") (pintype "passive"))
      (node (ref "R28") (pin "2") (pinfunction "2_2") (pintype "passive"))
    )
    (net (code "76") (name "Net-(P12-Pad1)") (class "Default")
      (node (ref "P12") (pin "1") (pinfunction "1_1") (pintype "passive"))
      (node (ref "R29") (pin "2") (pinfunction "2_2") (pintype "passive"))
    )
    (net (code "77") (name "Net-(P13-Pad1)") (class "Default")
      (node (ref "P13") (pin "1") (pinfunction "1_1") (pintype "passive"))
      (node (ref "R32") (pin "2") (pinfunction "2_2") (pintype "passive"))
    )
    (net (code "78") (name "Net-(P14-Pad3)") (class "Default")
      (node (ref "P14") (pin "3") (pinfunction "3_3") (pintype "passive"))
      (node (ref "R36") (pin "2") (pinfunction "2_2") (pintype "passive"))
    )
    (net (code "79") (name "Net-(Q2-B)") (class "Default")
      (node (ref "Q2") (pin "2") (pinfunction "B_2") (pintype "passive"))
      (node (ref "R20") (pin "2") (pinfunction "2_2") (pintype "passive"))
    )
    (net (code "80") (name "Net-(Q5-B)") (class "Default")
      (node (ref "Q5") (pin "2") (pinfunction "B_2") (pintype "passive"))
      (node (ref "R36") (pin "1") (pinfunction "1_1") (pintype "passive"))
    )
    (net (code "81") (name "Net-(U1A-PB2-BOOT1(PB2){slash}EVENTOUT)") (class "Default")
      (node (ref "R1") (pin "2") (pinfunction "2_2") (pintype "passive"))
      (node (ref "U1") (pin "28") (pinfunction "PB2-BOOT1(PB2)/EVENTOUT_28") (pintype "bidirectional"))
    )
    (net (code "82") (name "Net-(U1B-BOOT0{slash}VPP)") (class "Default")
      (node (ref "R6") (pin "2") (pinfunction "2_2") (pintype "passive"))
      (node (ref "U1") (pin "60") (pinfunction "BOOT0/VPP_60") (pintype "input"))
    )
    (net (code "83") (name "Net-(U1B-NRST)") (class "Default")
      (node (ref "C5") (pin "2") (pinfunction "2_2") (pintype "passive"))
      (node (ref "R4") (pin "1") (pinfunction "1_1") (pintype "passive"))
      (node (ref "SW1") (pin "2") (pinfunction "2_2") (pintype "passive"))
      (node (ref "U1") (pin "7") (pinfunction "NRST_7") (pintype "bidirectional"))
    )
    (net (code "84") (name "Net-(U1B-PH0-OSC_IN(PH0){slash}EVENTOUT{slash}OSC_IN)") (class "Default")
      (node (ref "C7") (pin "2") (pintype "passive"))
      (node (ref "U1") (pin "5") (pinfunction "PH0-OSC_IN(PH0)/EVENTOUT/OSC_IN_5") (pintype "bidirectional"))
      (node (ref "X1") (pin "2") (pinfunction "OSC2_2") (pintype "passive"))
    )
    (net (code "85") (name "Net-(U1B-PH1-OSC_OUT(PH1){slash}EVENTOUT{slash}OSC_OUT)") (class "Default")
      (node (ref "C6") (pin "2") (pintype "passive"))
      (node (ref "U1") (pin "6") (pinfunction "PH1-OSC_OUT(PH1)/EVENTOUT/OSC_OUT_6") (pintype "bidirectional"))
      (node (ref "X1") (pin "1") (pinfunction "OSC1_1") (pintype "passive"))
    )
    (net (code "86") (name "Net-(U3-CANH)") (class "Default")
      (node (ref "CAN1") (pin "2") (pinfunction "2_2") (pintype "passive"))
      (node (ref "R37") (pin "2") (pinfunction "2_2") (pintype "passive"))
      (node (ref "U3") (pin "7") (pinfunction "CANH_7") (pintype "bidirectional"))
    )
    (net (code "87") (name "Net-(U3-CANL)") (class "Default")
      (node (ref "CAN1") (pin "3") (pinfunction "3_3") (pintype "passive"))
      (node (ref "R37") (pin "1") (pinfunction "1_1") (pintype "passive"))
      (node (ref "U3") (pin "6") (pinfunction "CANL_6") (pintype "bidirectional"))
    )
    (net (code "88") (name "POWER") (class "Default")
      (node (ref "DC") (pin "1") (pinfunction "1_1") (pintype "passive"))
      (node (ref "R9") (pin "2") (pinfunction "2_2") (pintype "passive"))
    )
    (net (code "89") (name "VCC_DJ") (class "Default")
      (node (ref "DC") (pin "2") (pinfunction "2_2") (pintype "passive"))
      (node (ref "DC") (pin "3") (pinfunction "3_3") (pintype "passive"))
      (node (ref "P1") (pin "2") (pinfunction "2_2") (pintype "passive"))
      (node (ref "P10") (pin "2") (pinfunction "2_2") (pintype "passive"))
      (node (ref "P11") (pin "2") (pinfunction "2_2") (pintype "passive"))
      (node (ref "P12") (pin "2") (pinfunction "2_2") (pintype "passive"))
      (node (ref "P13") (pin "2") (pinfunction "2_2") (pintype "passive"))
      (node (ref "P2") (pin "2") (pinfunction "2_2") (pintype "passive"))
      (node (ref "P3") (pin "2") (pinfunction "2_2") (pintype "passive"))
      (node (ref "P5") (pin "2") (pinfunction "2_2") (pintype "passive"))
      (node (ref "P6") (pin "2") (pinfunction "2_2") (pintype "passive"))
      (node (ref "P7") (pin "2") (pinfunction "2_2") (pintype "passive"))
      (node (ref "P8") (pin "2") (pinfunction "2_2") (pintype "passive"))
      (node (ref "P9") (pin "2") (pinfunction "2_2") (pintype "passive"))
    )
    (net (code "90") (name "VG") (class "Default")
      (node (ref "IIC1") (pin "4") (pinfunction "4_4") (pintype "passive"))
      (node (ref "IIC2") (pin "4") (pinfunction "4_4") (pintype "passive"))
      (node (ref "IIC3") (pin "4") (pinfunction "4_4") (pintype "passive"))
      (node (ref "IIC4") (pin "4") (pinfunction "4_4") (pintype "passive"))
      (node (ref "SEL") (pin "3") (pinfunction "3_3") (pintype "passive"))
      (node (ref "SEL") (pin "4") (pinfunction "4_4") (pintype "passive"))
    )
    (net (code "91") (name "unconnected-(KEY-Pad3)") (class "Default")
      (node (ref "KEY") (pin "3") (pinfunction "3_3") (pintype "passive"))
    )
    (net (code "92") (name "unconnected-(U3-Vref-Pad5)") (class "Default")
      (node (ref "U3") (pin "5") (pinfunction "Vref_5") (pintype "output"))
    )
  )
)
